# Sheet1.net
KiCad netlist of a schematic drawn in Altium Designer
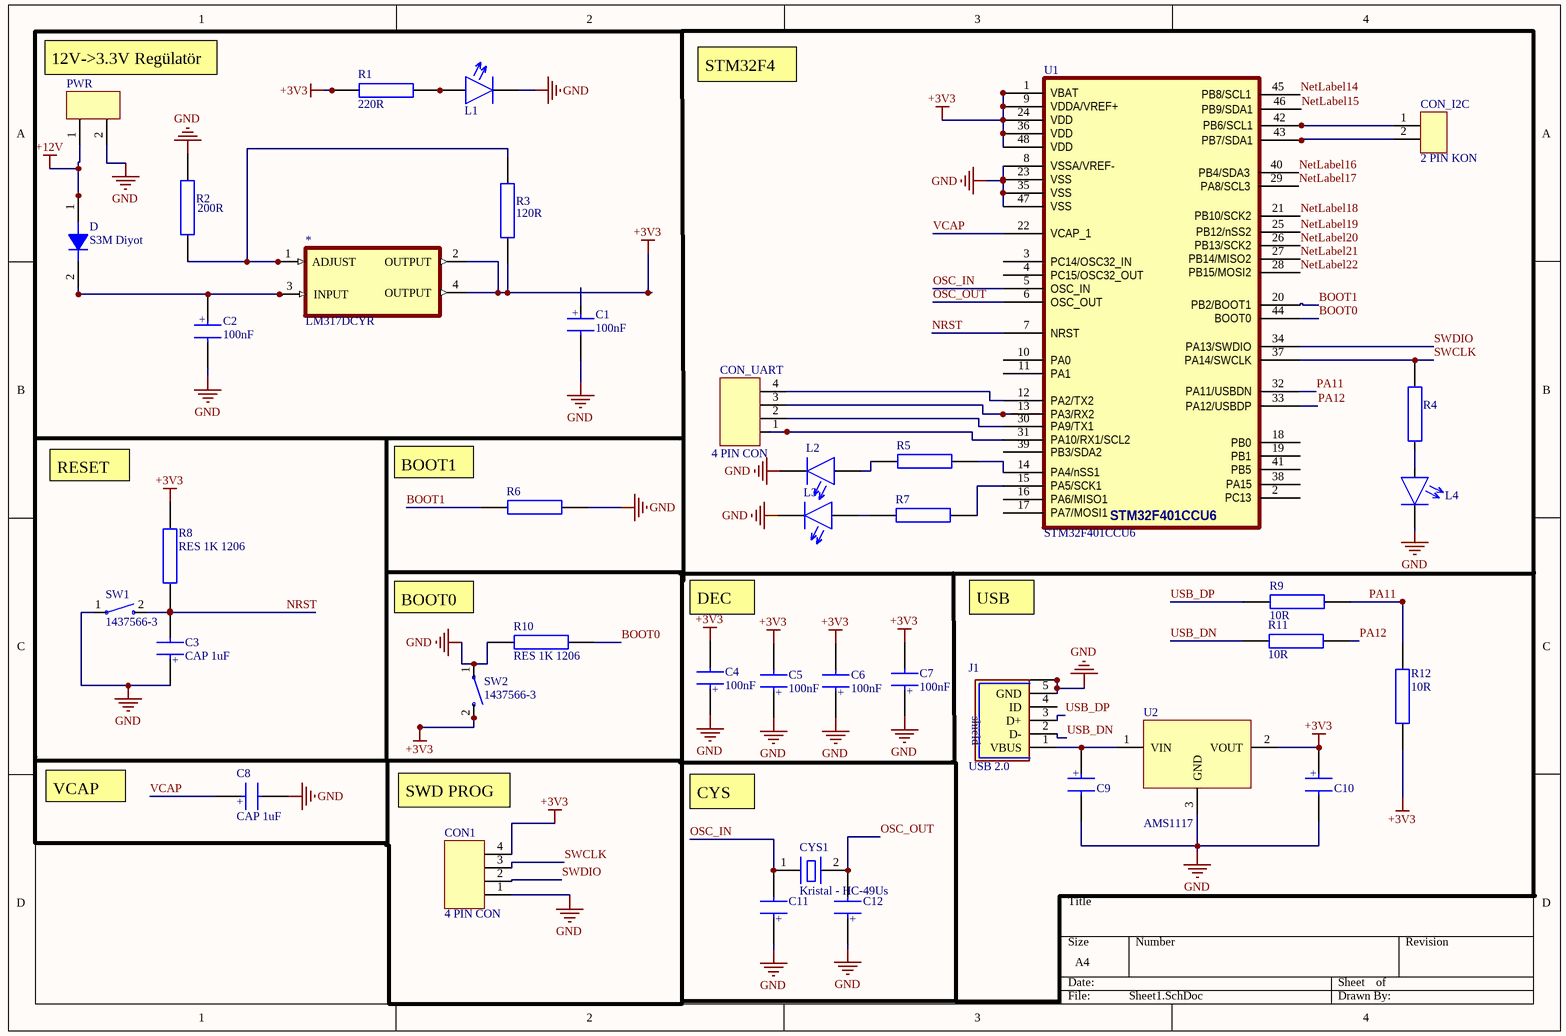
[diagram p0: Sheet1.SchDoc]

(export (version "E")
  (design (tool "Eeschema 10.0.6"))
  (components
    (comp (ref "*")
      (value "LM317DCYR")
      (footprint "SOT230P700X180-4N")
      (libsource (lib "Schlib") (part "LM317DCYR"))
    )
    (comp (ref "C1")
      (value "100nF")
      (footprint "CAP_805")
      (description "0805 smd")
      (libsource (lib "Udemy_Schlib1") (part "CAP 1uF"))
    )
    (comp (ref "C2")
      (value "100nF")
      (footprint "CAP_805")
      (description "0805 smd")
      (libsource (lib "Udemy_Schlib1") (part "CAP 1uF"))
    )
    (comp (ref "C3")
      (value "CAP 1uF")
      (footprint "CAP_805")
      (description "0805 smd")
      (libsource (lib "Udemy_Schlib1") (part "CAP 1uF"))
    )
    (comp (ref "C4")
      (value "100nF")
      (footprint "CAP_805")
      (description "0805 smd")
      (libsource (lib "Udemy_Schlib1") (part "CAP 1uF"))
    )
    (comp (ref "C5")
      (value "100nF")
      (footprint "CAP_805")
      (description "0805 smd")
      (libsource (lib "Udemy_Schlib1") (part "CAP 1uF"))
    )
    (comp (ref "C6")
      (value "100nF")
      (footprint "CAP_805")
      (description "0805 smd")
      (libsource (lib "Udemy_Schlib1") (part "CAP 1uF"))
    )
    (comp (ref "C7")
      (value "100nF")
      (footprint "CAP_805")
      (description "0805 smd")
      (libsource (lib "Udemy_Schlib1") (part "CAP 1uF"))
    )
    (comp (ref "C8")
      (value "CAP 1uF")
      (footprint "CAP_805")
      (description "0805 smd")
      (libsource (lib "Udemy_Schlib1") (part "CAP 1uF"))
    )
    (comp (ref "C9")
      (value "CAP 1uF")
      (footprint "CAP_805")
      (description "0805 smd")
      (libsource (lib "Udemy_Schlib1") (part "CAP 1uF"))
    )
    (comp (ref "C10")
      (value "CAP 1uF")
      (footprint "CAP_805")
      (description "0805 smd")
      (libsource (lib "Udemy_Schlib1") (part "CAP 1uF"))
    )
    (comp (ref "C11")
      (value "CAP 0.1uF")
      (footprint "CAP_805")
      (description "0805 smd")
      (libsource (lib "Udemy_Schlib1") (part "CAP 1uF"))
    )
    (comp (ref "C12")
      (value "CAP 1uF")
      (footprint "CAP_805")
      (description "0805 smd")
      (libsource (lib "Udemy_Schlib1") (part "CAP 1uF"))
    )
    (comp (ref "CON1")
      (value "4 PIN CON")
      (footprint "4 PIN 2.54MM")
      (description "2.54mm vertical connector")
      (libsource (lib "Udemy_Schlib1") (part "4 PIN CON"))
    )
    (comp (ref "CON_I2C")
      (value "2 PIN KON")
      (footprint "2 PIN 2.54MM")
      (description "2.54 mm vertical")
      (libsource (lib "Udemy_Schlib1") (part "2 PIN KON"))
    )
    (comp (ref "CON_UART")
      (value "4 PIN CON")
      (footprint "4 PIN 2.54MM")
      (description "2.54mm vertical connector")
      (libsource (lib "Udemy_Schlib1") (part "4 PIN CON"))
    )
    (comp (ref "CYS1")
      (value "Kristal - HC-49Us")
      (footprint "Kristal - HC-49Us -smd")
      (description "Smd tipi kristal")
      (libsource (lib "Udemy_Schlib1") (part "Kristal - HC-49Us"))
    )
    (comp (ref "D")
      (value "S3M Diyot")
      (footprint "DO214AA")
      (fields (field (name "VOLTAGE") "1000V"))
      (libsource (lib "Udemy_Schlib1") (part "S3M Diyot"))
    )
    (comp (ref "J1")
      (value "USB 2.0")
      (footprint "65100516121")
      (description "USB - mini B USB 2.0 Receptacle Connector 5 Position Surface Mount, Right Angle")
      (fields (field (name "MP") "65100516121") (field (name "MF") "WÃ¼rth Elektronik"))
      (libsource (lib "Schlib") (part "USB 2.0"))
    )
    (comp (ref "L1")
      (value "Led Red")
      (footprint "Led 1206")
      (libsource (lib "Udemy_Schlib1") (part "Led Red"))
    )
    (comp (ref "L2")
      (value "Led Red")
      (footprint "Led 1206")
      (libsource (lib "Udemy_Schlib1") (part "Led Red"))
    )
    (comp (ref "L3")
      (value "Led Red")
      (footprint "Led 1206")
      (libsource (lib "Udemy_Schlib1") (part "Led Red"))
    )
    (comp (ref "L4")
      (value "Led Red")
      (footprint "Led 1206")
      (libsource (lib "Udemy_Schlib1") (part "Led Red"))
    )
    (comp (ref "PWR")
      (value "2 Pin Klemens")
      (footprint "5.08mm-2 pin")
      (description "5.08mm 2 pin klemens")
      (libsource (lib "Udemy_Schlib1") (part "2 Pin Klemens"))
    )
    (comp (ref "R1")
      (value "220R")
      (footprint "RES_1206")
      (libsource (lib "Udemy_Schlib1") (part "RES 100R 1206"))
    )
    (comp (ref "R2")
      (value "200R")
      (footprint "RES_1206")
      (libsource (lib "Udemy_Schlib1") (part "RES 100R 1206"))
    )
    (comp (ref "R3")
      (value "120R")
      (footprint "RES_1206")
      (libsource (lib "Udemy_Schlib1") (part "RES 100R 1206"))
    )
    (comp (ref "R4")
      (value "RES 100R 1206")
      (footprint "RES_1206")
      (libsource (lib "Udemy_Schlib1") (part "RES 100R 1206"))
    )
    (comp (ref "R5")
      (value "RES 100R 1206")
      (footprint "RES_1206")
      (libsource (lib "Udemy_Schlib1") (part "RES 100R 1206"))
    )
    (comp (ref "R6")
      (value "RES 100R 1206")
      (footprint "RES_1206")
      (libsource (lib "Udemy_Schlib1") (part "RES 100R 1206"))
    )
    (comp (ref "R7")
      (value "RES 100R 1206")
      (footprint "RES_1206")
      (libsource (lib "Udemy_Schlib1") (part "RES 100R 1206"))
    )
    (comp (ref "R8")
      (value "RES 1K 1206")
      (footprint "RES_1206")
      (libsource (lib "Udemy_Schlib1") (part "RES 1K 1206"))
    )
    (comp (ref "R9")
      (value "10R")
      (footprint "RES_1206")
      (libsource (lib "Udemy_Schlib1") (part "RES 1K 1206"))
    )
    (comp (ref "R10")
      (value "RES 1K 1206")
      (footprint "RES_1206")
      (libsource (lib "Udemy_Schlib1") (part "RES 1K 1206"))
    )
    (comp (ref "R11")
      (value "10R")
      (footprint "RES_1206")
      (libsource (lib "Udemy_Schlib1") (part "RES 1K 1206"))
    )
    (comp (ref "R12")
      (value "10R")
      (footprint "RES_1206")
      (libsource (lib "Udemy_Schlib1") (part "RES 1K 1206"))
    )
    (comp (ref "SW1")
      (value "1437566-3")
      (footprint "SW_1437566-3")
      (description "Switch Tactile OFF (ON) SPST Rectangular Button Gull Wing 0.05A 12VDC SMD Loose Piece")
      (libsource (lib "Schlib") (part "1437566-3"))
    )
    (comp (ref "SW2")
      (value "1437566-3")
      (footprint "SW_1437566-3")
      (description "Switch Tactile OFF (ON) SPST Rectangular Button Gull Wing 0.05A 12VDC SMD Loose Piece")
      (libsource (lib "Schlib") (part "1437566-3"))
    )
    (comp (ref "U1")
      (value "STM32F401CCU6")
      (footprint "UFQFPN48")
      (libsource (lib "Schlib") (part "STM32F401CCU6"))
    )
    (comp (ref "U2")
      (value "AMS1117")
      (footprint "AMS1117")
      (description "3V3 Voltage Regulator")
      (libsource (lib "Udemy_Schlib1") (part "AMS1117"))
    )
  )
  (nets
    (net (code "1") (name "+3V3") (class "Default")
      (node (ref "*") (pin "2") (pinfunction "OUTPUT_2") (pintype "output"))
      (node (ref "*") (pin "4") (pinfunction "OUTPUT_4") (pintype "output"))
      (node (ref "C10") (pin "1") (pinfunction "1_1") (pintype "passive"))
      (node (ref "C4") (pin "2") (pinfunction "2_2") (pintype "passive"))
      (node (ref "C5") (pin "2") (pinfunction "2_2") (pintype "passive"))
      (node (ref "C6") (pin "2") (pinfunction "2_2") (pintype "passive"))
      (node (ref "C7") (pin "2") (pinfunction "2_2") (pintype "passive"))
      (node (ref "CON1") (pin "4") (pintype "passive"))
      (node (ref "R1") (pin "1") (pintype "passive"))
      (node (ref "R12") (pin "2") (pintype "passive"))
      (node (ref "R3") (pin "1") (pintype "passive"))
      (node (ref "R8") (pin "2") (pintype "passive"))
      (node (ref "SW2") (pin "2") (pinfunction "2_2") (pintype "passive"))
      (node (ref "U1") (pin "1") (pinfunction "VBAT_1") (pintype "passive"))
      (node (ref "U1") (pin "24") (pinfunction "VDD_24") (pintype "passive"))
      (node (ref "U1") (pin "36") (pinfunction "VDD_36") (pintype "passive"))
      (node (ref "U1") (pin "48") (pinfunction "VDD_48") (pintype "passive"))
      (node (ref "U1") (pin "9") (pinfunction "VDDA/VREF+_9") (pintype "passive"))
      (node (ref "U2") (pin "2") (pinfunction "VOUT_2") (pintype "passive"))
    )
    (net (code "2") (name "+12V") (class "Default")
      (node (ref "D") (pin "1") (pintype "passive"))
      (node (ref "PWR") (pin "1") (pintype "passive"))
    )
    (net (code "3") (name "/BOOT0") (class "Default")
      (node (ref "R10") (pin "1") (pintype "passive"))
      (node (ref "U1") (pin "44") (pinfunction "BOOT0_44") (pintype "passive"))
    )
    (net (code "4") (name "/BOOT1") (class "Default")
      (node (ref "R6") (pin "1") (pintype "passive"))
      (node (ref "U1") (pin "20") (pinfunction "PB2/BOOT1_20") (pintype "passive"))
    )
    (net (code "5") (name "/NRST") (class "Default")
      (node (ref "C3") (pin "2") (pinfunction "2_2") (pintype "passive"))
      (node (ref "R8") (pin "1") (pintype "passive"))
      (node (ref "SW1") (pin "2") (pinfunction "2_2") (pintype "passive"))
      (node (ref "U1") (pin "7") (pinfunction "NRST_7") (pintype "passive"))
    )
    (net (code "6") (name "/NetLabel14") (class "Default")
      (node (ref "U1") (pin "45") (pinfunction "PB8/SCL1_45") (pintype "passive"))
    )
    (net (code "7") (name "/NetLabel15") (class "Default")
      (node (ref "U1") (pin "46") (pinfunction "PB9/SDA1_46") (pintype "passive"))
    )
    (net (code "8") (name "/NetLabel16") (class "Default")
      (node (ref "U1") (pin "40") (pinfunction "PB4/SDA3_40") (pintype "passive"))
    )
    (net (code "9") (name "/NetLabel17") (class "Default")
      (node (ref "U1") (pin "29") (pinfunction "PA8/SCL3_29") (pintype "passive"))
    )
    (net (code "10") (name "/NetLabel18") (class "Default")
      (node (ref "U1") (pin "21") (pinfunction "PB10/SCK2_21") (pintype "passive"))
    )
    (net (code "11") (name "/NetLabel19") (class "Default")
      (node (ref "U1") (pin "25") (pinfunction "PB12/nSS2_25") (pintype "passive"))
    )
    (net (code "12") (name "/NetLabel20") (class "Default")
      (node (ref "U1") (pin "26") (pinfunction "PB13/SCK2_26") (pintype "passive"))
    )
    (net (code "13") (name "/NetLabel21") (class "Default")
      (node (ref "U1") (pin "27") (pinfunction "PB14/MISO2_27") (pintype "passive"))
    )
    (net (code "14") (name "/NetLabel22") (class "Default")
      (node (ref "U1") (pin "28") (pinfunction "PB15/MOSI2_28") (pintype "passive"))
    )
    (net (code "15") (name "/OSC_IN") (class "Default")
      (node (ref "C11") (pin "2") (pinfunction "2_2") (pintype "passive"))
      (node (ref "CYS1") (pin "1") (pintype "passive"))
      (node (ref "U1") (pin "5") (pinfunction "OSC_IN_5") (pintype "passive"))
    )
    (net (code "16") (name "/OSC_OUT") (class "Default")
      (node (ref "C12") (pin "2") (pinfunction "2_2") (pintype "passive"))
      (node (ref "CYS1") (pin "2") (pintype "passive"))
      (node (ref "U1") (pin "6") (pinfunction "OSC_OUT_6") (pintype "passive"))
    )
    (net (code "17") (name "/PA11") (class "Default")
      (node (ref "R12") (pin "1") (pintype "passive"))
      (node (ref "R9") (pin "2") (pintype "passive"))
      (node (ref "U1") (pin "32") (pinfunction "PA11/USBDN_32") (pintype "passive"))
    )
    (net (code "18") (name "/PA12") (class "Default")
      (node (ref "R11") (pin "2") (pintype "passive"))
      (node (ref "U1") (pin "33") (pinfunction "PA12/USBDP_33") (pintype "passive"))
    )
    (net (code "19") (name "/SWCLK") (class "Default")
      (node (ref "CON1") (pin "3") (pintype "passive"))
      (node (ref "R4") (pin "2") (pintype "passive"))
      (node (ref "U1") (pin "37") (pinfunction "PA14/SWCLK_37") (pintype "passive"))
    )
    (net (code "20") (name "/SWDIO") (class "Default")
      (node (ref "CON1") (pin "2") (pintype "passive"))
      (node (ref "U1") (pin "34") (pinfunction "PA13/SWDIO_34") (pintype "passive"))
    )
    (net (code "21") (name "/USB_DN") (class "Default")
      (node (ref "J1") (pin "2") (pinfunction "D-_2") (pintype "passive"))
      (node (ref "R11") (pin "1") (pintype "passive"))
    )
    (net (code "22") (name "/USB_DP") (class "Default")
      (node (ref "J1") (pin "3") (pinfunction "D+_3") (pintype "passive"))
      (node (ref "R9") (pin "1") (pintype "passive"))
    )
    (net (code "23") (name "/VCAP") (class "Default")
      (node (ref "C8") (pin "1") (pinfunction "1_1") (pintype "passive"))
      (node (ref "U1") (pin "22") (pinfunction "VCAP_1_22") (pintype "passive"))
    )
    (net (code "24") (name "GND") (class "Default")
      (node (ref "C1") (pin "2") (pinfunction "2_2") (pintype "passive"))
      (node (ref "C10") (pin "2") (pinfunction "2_2") (pintype "passive"))
      (node (ref "C11") (pin "1") (pinfunction "1_1") (pintype "passive"))
      (node (ref "C12") (pin "1") (pinfunction "1_1") (pintype "passive"))
      (node (ref "C2") (pin "2") (pinfunction "2_2") (pintype "passive"))
      (node (ref "C3") (pin "1") (pinfunction "1_1") (pintype "passive"))
      (node (ref "C4") (pin "1") (pinfunction "1_1") (pintype "passive"))
      (node (ref "C5") (pin "1") (pinfunction "1_1") (pintype "passive"))
      (node (ref "C6") (pin "1") (pinfunction "1_1") (pintype "passive"))
      (node (ref "C7") (pin "1") (pinfunction "1_1") (pintype "passive"))
      (node (ref "C8") (pin "2") (pinfunction "2_2") (pintype "passive"))
      (node (ref "C9") (pin "2") (pinfunction "2_2") (pintype "passive"))
      (node (ref "CON1") (pin "1") (pintype "passive"))
      (node (ref "J1") (pin "5") (pinfunction "GND_5") (pintype "passive"))
      (node (ref "J1") (pin "S1") (pinfunction "SHIELD_S1") (pintype "passive"))
      (node (ref "J1") (pin "S2") (pinfunction "SHIELD_S2") (pintype "passive"))
      (node (ref "J1") (pin "S3") (pinfunction "SHIELD_S3") (pintype "passive"))
      (node (ref "J1") (pin "S4") (pinfunction "SHIELD_S4") (pintype "passive"))
      (node (ref "L1") (pin "2") (pintype "passive"))
      (node (ref "L2") (pin "2") (pintype "passive"))
      (node (ref "L3") (pin "2") (pintype "passive"))
      (node (ref "L4") (pin "2") (pintype "passive"))
      (node (ref "PWR") (pin "2") (pintype "passive"))
      (node (ref "R10") (pin "2") (pintype "passive"))
      (node (ref "R2") (pin "2") (pintype "passive"))
      (node (ref "R6") (pin "2") (pintype "passive"))
      (node (ref "SW1") (pin "1") (pinfunction "1_1") (pintype "passive"))
      (node (ref "SW2") (pin "1") (pinfunction "1_1") (pintype "passive"))
      (node (ref "U1") (pin "23") (pinfunction "VSS_23") (pintype "passive"))
      (node (ref "U1") (pin "35") (pinfunction "VSS_35") (pintype "passive"))
      (node (ref "U1") (pin "47") (pinfunction "VSS_47") (pintype "passive"))
      (node (ref "U1") (pin "8") (pinfunction "VSSA/VREF-_8") (pintype "passive"))
      (node (ref "U2") (pin "3") (pinfunction "GND_3") (pintype "passive"))
    )
    (net (code "25") (name "Net-(*-ADJUST)") (class "Default")
      (node (ref "*") (pin "1") (pinfunction "ADJUST_1") (pintype "input"))
      (node (ref "R2") (pin "1") (pintype "passive"))
      (node (ref "R3") (pin "2") (pintype "passive"))
    )
    (net (code "26") (name "Net-(*-INPUT)") (class "Default")
      (node (ref "*") (pin "3") (pinfunction "INPUT_3") (pintype "input"))
      (node (ref "C2") (pin "1") (pinfunction "1_1") (pintype "passive"))
      (node (ref "D") (pin "2") (pintype "passive"))
    )
    (net (code "27") (name "Net-(J1-VBUS)") (class "Default")
      (node (ref "C9") (pin "1") (pinfunction "1_1") (pintype "passive"))
      (node (ref "J1") (pin "1") (pinfunction "VBUS_1") (pintype "passive"))
      (node (ref "U2") (pin "1") (pinfunction "VIN_1") (pintype "passive"))
    )
    (net (code "28") (name "Net-(L1-Pad1)") (class "Default")
      (node (ref "L1") (pin "1") (pintype "passive"))
      (node (ref "R1") (pin "2") (pintype "passive"))
    )
    (net (code "29") (name "Net-(L2-Pad1)") (class "Default")
      (node (ref "L2") (pin "1") (pintype "passive"))
      (node (ref "R5") (pin "1") (pintype "passive"))
    )
    (net (code "30") (name "Net-(L3-Pad1)") (class "Default")
      (node (ref "L3") (pin "1") (pintype "passive"))
      (node (ref "R7") (pin "1") (pintype "passive"))
    )
    (net (code "31") (name "Net-(L4-Pad1)") (class "Default")
      (node (ref "L4") (pin "1") (pintype "passive"))
      (node (ref "R4") (pin "1") (pintype "passive"))
    )
    (net (code "32") (name "Net-(U1-PA2{slash}TX2)") (class "Default")
      (node (ref "CON_UART") (pin "4") (pintype "passive"))
      (node (ref "U1") (pin "12") (pinfunction "PA2/TX2_12") (pintype "passive"))
    )
    (net (code "33") (name "Net-(U1-PA3{slash}RX2)") (class "Default")
      (node (ref "CON_UART") (pin "3") (pintype "passive"))
      (node (ref "U1") (pin "13") (pinfunction "PA3/RX2_13") (pintype "passive"))
    )
    (net (code "34") (name "Net-(U1-PA4{slash}nSS1)") (class "Default")
      (node (ref "R5") (pin "2") (pintype "passive"))
      (node (ref "U1") (pin "14") (pinfunction "PA4/nSS1_14") (pintype "passive"))
    )
    (net (code "35") (name "Net-(U1-PA5{slash}SCK1)") (class "Default")
      (node (ref "R7") (pin "2") (pintype "passive"))
      (node (ref "U1") (pin "15") (pinfunction "PA5/SCK1_15") (pintype "passive"))
    )
    (net (code "36") (name "Net-(U1-PA9{slash}TX1)") (class "Default")
      (node (ref "CON_UART") (pin "2") (pintype "passive"))
      (node (ref "U1") (pin "30") (pinfunction "PA9/TX1_30") (pintype "passive"))
    )
    (net (code "37") (name "Net-(U1-PA10{slash}RX1{slash}SCL2)") (class "Default")
      (node (ref "CON_UART") (pin "1") (pintype "passive"))
      (node (ref "U1") (pin "31") (pinfunction "PA10/RX1/SCL2_31") (pintype "passive"))
    )
    (net (code "38") (name "Net-(U1-PB6{slash}SCL1)") (class "Default")
      (node (ref "CON_I2C") (pin "1") (pintype "passive"))
      (node (ref "U1") (pin "42") (pinfunction "PB6/SCL1_42") (pintype "passive"))
    )
    (net (code "39") (name "Net-(U1-PB7{slash}SDA1)") (class "Default")
      (node (ref "CON_I2C") (pin "2") (pintype "passive"))
      (node (ref "U1") (pin "43") (pinfunction "PB7/SDA1_43") (pintype "passive"))
    )
    (net (code "40") (name "unconnected-(C1-Pad1)") (class "Default")
      (node (ref "C1") (pin "1") (pinfunction "1_1") (pintype "passive"))
    )
    (net (code "41") (name "unconnected-(J1-ID-Pad4)") (class "Default")
      (node (ref "J1") (pin "4") (pinfunction "ID_4") (pintype "passive"))
    )
    (net (code "42") (name "unconnected-(U1-PA0-Pad10)") (class "Default")
      (node (ref "U1") (pin "10") (pinfunction "PA0_10") (pintype "passive"))
    )
    (net (code "43") (name "unconnected-(U1-PA1-Pad11)") (class "Default")
      (node (ref "U1") (pin "11") (pinfunction "PA1_11") (pintype "passive"))
    )
    (net (code "44") (name "unconnected-(U1-PA6{slash}MISO1-Pad16)") (class "Default")
      (node (ref "U1") (pin "16") (pinfunction "PA6/MISO1_16") (pintype "passive"))
    )
    (net (code "45") (name "unconnected-(U1-PA7{slash}MOSI1-Pad17)") (class "Default")
      (node (ref "U1") (pin "17") (pinfunction "PA7/MOSI1_17") (pintype "passive"))
    )
    (net (code "46") (name "unconnected-(U1-PA15-Pad38)") (class "Default")
      (node (ref "U1") (pin "38") (pinfunction "PA15_38") (pintype "passive"))
    )
    (net (code "47") (name "unconnected-(U1-PB0-Pad18)") (class "Default")
      (node (ref "U1") (pin "18") (pinfunction "PB0_18") (pintype "passive"))
    )
    (net (code "48") (name "unconnected-(U1-PB1-Pad19)") (class "Default")
      (node (ref "U1") (pin "19") (pinfunction "PB1_19") (pintype "passive"))
    )
    (net (code "49") (name "unconnected-(U1-PB3{slash}SDA2-Pad39)") (class "Default")
      (node (ref "U1") (pin "39") (pinfunction "PB3/SDA2_39") (pintype "passive"))
    )
    (net (code "50") (name "unconnected-(U1-PB5-Pad41)") (class "Default")
      (node (ref "U1") (pin "41") (pinfunction "PB5_41") (pintype "passive"))
    )
    (net (code "51") (name "unconnected-(U1-PC13-Pad2)") (class "Default")
      (node (ref "U1") (pin "2") (pinfunction "PC13_2") (pintype "passive"))
    )
    (net (code "52") (name "unconnected-(U1-PC14{slash}OSC32_IN-Pad3)") (class "Default")
      (node (ref "U1") (pin "3") (pinfunction "PC14/OSC32_IN_3") (pintype "passive"))
    )
    (net (code "53") (name "unconnected-(U1-PC15{slash}OSC32_OUT-Pad4)") (class "Default")
      (node (ref "U1") (pin "4") (pinfunction "PC15/OSC32_OUT_4") (pintype "passive"))
    )
  )
)
